# Temp_sensor.net
KiCad netlist of a schematic drawn in Altium Designer
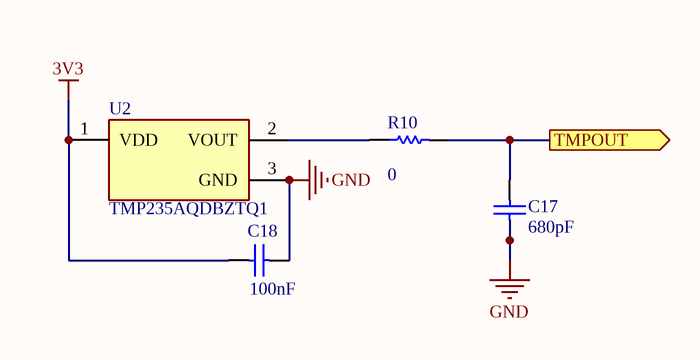
[diagram p0: Temp sensor.SchDoc]

(export (version "E")
  (design (tool "Eeschema 10.0.6"))
  (components
    (comp (ref "C17")
      (value "680pF")
      (footprint "1608[0603]")
      (description "Capacitor")
      (fields (field (name "Comment") "Cap") (field (name "PUBLISHER") "Altium Limited"))
      (libsource (lib "Miscellaneous Devices") (part "Cap"))
    )
    (comp (ref "C18")
      (value "100nF")
      (footprint "1608[0603]")
      (description "Capacitor")
      (fields (field (name "Comment") "Cap") (field (name "PUBLISHER") "Altium Limited"))
      (libsource (lib "Miscellaneous Devices") (part "Cap"))
    )
    (comp (ref "R10")
      (value "0")
      (footprint "0402-A")
      (description "Resistor")
      (fields (field (name "Comment") "Res1") (field (name "PUBLISHER") "Altium Limited"))
      (libsource (lib "Miscellaneous Devices") (part "Res1"))
    )
    (comp (ref "U2")
      (value "TMP235AQDBZTQ1")
      (footprint "FP-DBZ0003A-MFG")
      (description "LOW-POWER HIGH-ACCURACY ANALOG O")
      (fields
        (field (name "MANUFACTURER") "Texas Instruments")
        (field (name "MANUFACTURER PART NUMBER") "TMP235A2DBZR")
      )
      (libsource (lib "Altium Content Vault") (part "1212246baba8f64ab0dd7b63bd818eb"))
    )
  )
  (nets
    (net (code "1") (name "/TMPOUT") (class "Default")
      (node (ref "C17") (pin "1") (pinfunction "1_1") (pintype "passive"))
      (node (ref "R10") (pin "2") (pinfunction "2_2") (pintype "passive"))
    )
    (net (code "2") (name "3V3") (class "Default")
      (node (ref "C18") (pin "1") (pinfunction "1_1") (pintype "passive"))
      (node (ref "U2") (pin "1") (pinfunction "VDD_1") (pintype "power_in"))
    )
    (net (code "3") (name "GND") (class "Default")
      (node (ref "C17") (pin "2") (pinfunction "2_2") (pintype "passive"))
      (node (ref "C18") (pin "2") (pinfunction "2_2") (pintype "passive"))
      (node (ref "U2") (pin "3") (pinfunction "GND_3") (pintype "power_in"))
    )
    (net (code "4") (name "Net-(U2-VOUT)") (class "Default")
      (node (ref "R10") (pin "1") (pinfunction "1_1") (pintype "passive"))
      (node (ref "U2") (pin "2") (pinfunction "VOUT_2") (pintype "passive"))
    )
  )
)
